# Sheet1.net
KiCad netlist of a schematic drawn in Altium Designer
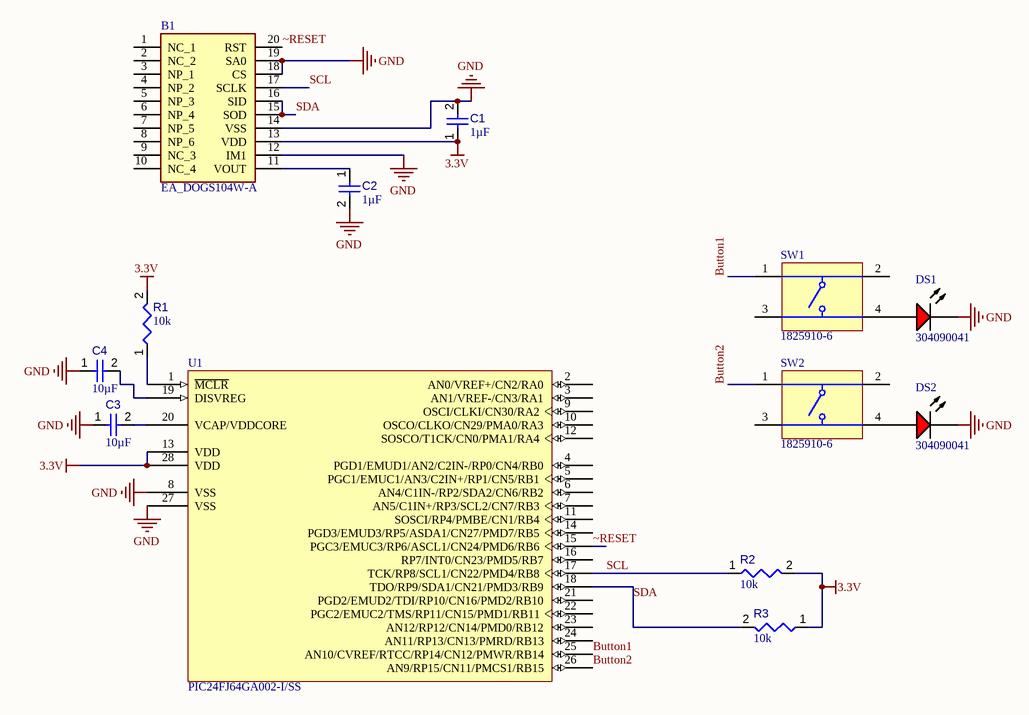
[diagram p0: Sheet1.SchDoc]

(export (version "E")
  (design (tool "Eeschema 10.0.6"))
  (components
    (comp (ref "B1")
      (value "EA_DOGS104W-A")
      (footprint "DIP2540W50P254L3600H260Q20N")
      (description "LED Backlighting LCD MODULE 4X10 WH BKGRND RFLT 2.6mm")
      (fields
        (field (name "MOUSER PART NUMBER") "790-EADOGS104W-A")
        (field (name "MANUFACTURER_PART_NUMBER") "EA DOGS104W-A")
      )
      (libsource (lib "EA_DOGS104W-A") (part "EA_DOGS104W-A"))
    )
    (comp (ref "C1")
      (value "1µF")
      (footprint "CAPC2013X135X45NL10T25")
      (description "Chip Capacitor, 1 uF, +/- 10%, 50 V, 0805 (2012 Metric)")
      (fields (field (name "TOLERANCE") "10%") (field (name "Comment") "Capacitor 1 uF +/- 10% 50 V 0805"))
      (libsource (lib "Egeree Gemta Workspace") (part "CAP-NP-2"))
    )
    (comp (ref "C2")
      (value "1µF")
      (footprint "CAPC2013X135X45NL10T25")
      (description "Chip Capacitor, 1 uF, +/- 10%, 50 V, 0805 (2012 Metric)")
      (fields (field (name "TOLERANCE") "10%") (field (name "Comment") "Capacitor 1 uF +/- 10% 50 V 0805"))
      (libsource (lib "Egeree Gemta Workspace") (part "CAP-NP-2"))
    )
    (comp (ref "C3")
      (value "10µF")
      (footprint "CAPC3216X180X50NL20T25")
      (description "Chip Capacitor, 10 uF, +/- 10%, 16 V, 1206 (3216 Metric)")
      (fields (field (name "TOLERANCE") "10%") (field (name "Comment") "Capacitor 10 uF +/- 10% 16 V 1206"))
      (libsource (lib "Egeree Gemta Workspace") (part "CAP-NP-2"))
    )
    (comp (ref "C4")
      (value "10µF")
      (footprint "CAPC3216X180X50NL20T25")
      (description "Chip Capacitor, 10 uF, +/- 10%, 16 V, 1206 (3216 Metric)")
      (fields (field (name "TOLERANCE") "10%") (field (name "Comment") "Capacitor 10 uF +/- 10% 16 V 1206"))
      (libsource (lib "Egeree Gemta Workspace") (part "CAP-NP-2"))
    )
    (comp (ref "DS1")
      (value "304090041")
      (footprint "LED-2P-2.28-3MM_A")
      (description "Red LED, 80 mW, 30 mA, -25 to 85 degC, 2-Pin THD")
      (fields (field (name "MANUFACTURER") "Shenzhen CGX"))
      (libsource (lib "Egeree Gemta Workspace") (part "LED-RED-AK-2"))
    )
    (comp (ref "DS2")
      (value "304090041")
      (footprint "LED-2P-2.28-3MM_A")
      (description "Red LED, 80 mW, 30 mA, -25 to 85 degC, 2-Pin THD")
      (fields (field (name "MANUFACTURER") "Shenzhen CGX"))
      (libsource (lib "Egeree Gemta Workspace") (part "LED-RED-AK-2"))
    )
    (comp (ref "R1")
      (value "10k")
      (footprint "RESC0402(1005)_L")
      (description "10K 0.063W 1% 0402 (1005 Metric)  SMD")
      (fields (field (name "POWER") "63mW") (field (name "TOLERANCE") "1%"))
      (libsource (lib "Egeree Gemta Workspace") (part "10KR2F"))
    )
    (comp (ref "R2")
      (value "10k")
      (footprint "RESC0402(1005)_L")
      (description "10K 0.063W 1% 0402 (1005 Metric)  SMD")
      (fields (field (name "POWER") "63mW") (field (name "TOLERANCE") "1%"))
      (libsource (lib "Egeree Gemta Workspace") (part "10KR2F"))
    )
    (comp (ref "R3")
      (value "10k")
      (footprint "RESC0402(1005)_L")
      (description "10K 0.063W 1% 0402 (1005 Metric)  SMD")
      (fields (field (name "POWER") "63mW") (field (name "TOLERANCE") "1%"))
      (libsource (lib "Egeree Gemta Workspace") (part "10KR2F"))
    )
    (comp (ref "SW1")
      (value "1825910-6")
      (footprint "TECO-1825910-6_V")
      (description "Tact Switch, SPST-NO, 0.05 A, -35 to 85 degC, 4-Pin THD, RoHS, Bulk")
      (fields (field (name "MANUFACTURER") "TE Connectivity"))
      (libsource (lib "Altium Content Vault") (part "SW-SPST-4_A"))
    )
    (comp (ref "SW2")
      (value "1825910-6")
      (footprint "TECO-1825910-6_V")
      (description "Tact Switch, SPST-NO, 0.05 A, -35 to 85 degC, 4-Pin THD, RoHS, Bulk")
      (fields (field (name "MANUFACTURER") "TE Connectivity"))
      (libsource (lib "Altium Content Vault") (part "SW-SPST-4_A"))
    )
    (comp (ref "U1")
      (value "PIC24FJ64GA002-I/SS")
      (footprint "SSOP-SS28_L")
      (libsource (lib "Altium Content Vault") (part "MC-16B-16GA002-SOIC28"))
    )
  )
  (nets
    (net (code "1") (name "/Button1") (class "Default")
      (node (ref "SW1") (pin "1") (pinfunction "1_1") (pintype "passive"))
      (node (ref "U1") (pin "25") (pinfunction "AN10/CVREF/RTCC/RP14/CN12/PMWR/RB14_25") (pintype "bidirectional"))
    )
    (net (code "2") (name "/Button2") (class "Default")
      (node (ref "SW2") (pin "1") (pinfunction "1_1") (pintype "passive"))
      (node (ref "U1") (pin "26") (pinfunction "AN9/RP15/CN11/PMCS1/RB15_26") (pintype "bidirectional"))
    )
    (net (code "3") (name "/SCL") (class "Default")
      (node (ref "B1") (pin "17") (pinfunction "SCLK_17") (pintype "passive"))
      (node (ref "R2") (pin "1") (pinfunction "1_1") (pintype "passive"))
      (node (ref "U1") (pin "17") (pinfunction "TCK/RP8/SCL1/CN22/PMD4/RB8_17") (pintype "bidirectional"))
    )
    (net (code "4") (name "/SDA") (class "Default")
      (node (ref "B1") (pin "15") (pinfunction "SOD_15") (pintype "passive"))
      (node (ref "B1") (pin "16") (pinfunction "SID_16") (pintype "passive"))
      (node (ref "R3") (pin "2") (pinfunction "2_2") (pintype "passive"))
      (node (ref "U1") (pin "18") (pinfunction "TDO/RP9/SDA1/CN21/PMD3/RB9_18") (pintype "bidirectional"))
    )
    (net (code "5") (name "/~RESET") (class "Default")
      (node (ref "B1") (pin "20") (pinfunction "RST_20") (pintype "passive"))
      (node (ref "U1") (pin "15") (pinfunction "PGC3/EMUC3/RP6/ASCL1/CN24/PMD6/RB6_15") (pintype "bidirectional"))
    )
    (net (code "6") (name "3.3V") (class "Default")
      (node (ref "B1") (pin "13") (pinfunction "VDD_13") (pintype "passive"))
      (node (ref "C1") (pin "1") (pinfunction "1_1") (pintype "passive"))
      (node (ref "R1") (pin "2") (pinfunction "2_2") (pintype "passive"))
      (node (ref "R2") (pin "2") (pinfunction "2_2") (pintype "passive"))
      (node (ref "R3") (pin "1") (pinfunction "1_1") (pintype "passive"))
      (node (ref "U1") (pin "13") (pinfunction "VDD_13") (pintype "power_in"))
      (node (ref "U1") (pin "28") (pinfunction "VDD_28") (pintype "power_in"))
    )
    (net (code "7") (name "GND") (class "Default")
      (node (ref "B1") (pin "12") (pinfunction "IM1_12") (pintype "passive"))
      (node (ref "B1") (pin "14") (pinfunction "VSS_14") (pintype "passive"))
      (node (ref "B1") (pin "18") (pinfunction "CS_18") (pintype "passive"))
      (node (ref "B1") (pin "19") (pinfunction "SA0_19") (pintype "passive"))
      (node (ref "C1") (pin "2") (pinfunction "2_2") (pintype "passive"))
      (node (ref "C2") (pin "2") (pinfunction "2_2") (pintype "passive"))
      (node (ref "C3") (pin "1") (pinfunction "1_1") (pintype "passive"))
      (node (ref "C4") (pin "1") (pinfunction "1_1") (pintype "passive"))
      (node (ref "DS1") (pin "2") (pinfunction "K_2") (pintype "passive"))
      (node (ref "DS2") (pin "2") (pinfunction "K_2") (pintype "passive"))
      (node (ref "U1") (pin "27") (pinfunction "VSS_27") (pintype "power_in"))
      (node (ref "U1") (pin "8") (pinfunction "VSS_8") (pintype "power_in"))
    )
    (net (code "8") (name "Net-(B1-VOUT)") (class "Default")
      (node (ref "B1") (pin "11") (pinfunction "VOUT_11") (pintype "passive"))
      (node (ref "C2") (pin "1") (pinfunction "1_1") (pintype "passive"))
    )
    (net (code "9") (name "Net-(DS1-A)") (class "Default")
      (node (ref "DS1") (pin "1") (pinfunction "A_1") (pintype "passive"))
      (node (ref "SW1") (pin "4") (pinfunction "4_4") (pintype "passive"))
    )
    (net (code "10") (name "Net-(DS2-A)") (class "Default")
      (node (ref "DS2") (pin "1") (pinfunction "A_1") (pintype "passive"))
      (node (ref "SW2") (pin "4") (pinfunction "4_4") (pintype "passive"))
    )
    (net (code "11") (name "Net-(U1-DISVREG)") (class "Default")
      (node (ref "C4") (pin "2") (pinfunction "2_2") (pintype "passive"))
      (node (ref "U1") (pin "19") (pinfunction "DISVREG_19") (pintype "input"))
    )
    (net (code "12") (name "Net-(U1-VCAP{slash}VDDCORE)") (class "Default")
      (node (ref "C3") (pin "2") (pinfunction "2_2") (pintype "passive"))
      (node (ref "U1") (pin "20") (pinfunction "VCAP/VDDCORE_20") (pintype "power_in"))
    )
    (net (code "13") (name "Net-(U1-~{MCLR})") (class "Default")
      (node (ref "R1") (pin "1") (pinfunction "1_1") (pintype "passive"))
      (node (ref "U1") (pin "1") (pinfunction "~{MCLR}_1") (pintype "input"))
    )
    (net (code "14") (name "unconnected-(B1-NC_1-Pad1)") (class "Default")
      (node (ref "B1") (pin "1") (pinfunction "NC_1_1") (pintype "passive"))
    )
    (net (code "15") (name "unconnected-(B1-NC_2-Pad2)") (class "Default")
      (node (ref "B1") (pin "2") (pinfunction "NC_2_2") (pintype "passive"))
    )
    (net (code "16") (name "unconnected-(B1-NC_3-Pad9)") (class "Default")
      (node (ref "B1") (pin "9") (pinfunction "NC_3_9") (pintype "passive"))
    )
    (net (code "17") (name "unconnected-(B1-NC_4-Pad10)") (class "Default")
      (node (ref "B1") (pin "10") (pinfunction "NC_4_10") (pintype "passive"))
    )
    (net (code "18") (name "unconnected-(B1-NP_1-Pad3)") (class "Default")
      (node (ref "B1") (pin "3") (pinfunction "NP_1_3") (pintype "passive"))
    )
    (net (code "19") (name "unconnected-(B1-NP_2-Pad4)") (class "Default")
      (node (ref "B1") (pin "4") (pinfunction "NP_2_4") (pintype "passive"))
    )
    (net (code "20") (name "unconnected-(B1-NP_3-Pad5)") (class "Default")
      (node (ref "B1") (pin "5") (pinfunction "NP_3_5") (pintype "passive"))
    )
    (net (code "21") (name "unconnected-(B1-NP_4-Pad6)") (class "Default")
      (node (ref "B1") (pin "6") (pinfunction "NP_4_6") (pintype "passive"))
    )
    (net (code "22") (name "unconnected-(B1-NP_5-Pad7)") (class "Default")
      (node (ref "B1") (pin "7") (pinfunction "NP_5_7") (pintype "passive"))
    )
    (net (code "23") (name "unconnected-(B1-NP_6-Pad8)") (class "Default")
      (node (ref "B1") (pin "8") (pinfunction "NP_6_8") (pintype "passive"))
    )
    (net (code "24") (name "unconnected-(SW1-Pad2)") (class "Default")
      (node (ref "SW1") (pin "2") (pinfunction "2_2") (pintype "passive"))
    )
    (net (code "25") (name "unconnected-(SW1-Pad3)") (class "Default")
      (node (ref "SW1") (pin "3") (pinfunction "3_3") (pintype "passive"))
    )
    (net (code "26") (name "unconnected-(SW2-Pad2)") (class "Default")
      (node (ref "SW2") (pin "2") (pinfunction "2_2") (pintype "passive"))
    )
    (net (code "27") (name "unconnected-(SW2-Pad3)") (class "Default")
      (node (ref "SW2") (pin "3") (pinfunction "3_3") (pintype "passive"))
    )
    (net (code "28") (name "unconnected-(U1-AN0{slash}VREF+{slash}CN2{slash}RA0-Pad2)") (class "Default")
      (node (ref "U1") (pin "2") (pinfunction "AN0/VREF+/CN2/RA0_2") (pintype "bidirectional"))
    )
    (net (code "29") (name "unconnected-(U1-AN1{slash}VREF-{slash}CN3{slash}RA1-Pad3)") (class "Default")
      (node (ref "U1") (pin "3") (pinfunction "AN1/VREF-/CN3/RA1_3") (pintype "bidirectional"))
    )
    (net (code "30") (name "unconnected-(U1-AN4{slash}C1IN-{slash}RP2{slash}SDA2{slash}CN6{slash}RB2-Pad6)") (class "Default")
      (node (ref "U1") (pin "6") (pinfunction "AN4/C1IN-/RP2/SDA2/CN6/RB2_6") (pintype "bidirectional"))
    )
    (net (code "31") (name "unconnected-(U1-AN5{slash}C1IN+{slash}RP3{slash}SCL2{slash}CN7{slash}RB3-Pad7)") (class "Default")
      (node (ref "U1") (pin "7") (pinfunction "AN5/C1IN+/RP3/SCL2/CN7/RB3_7") (pintype "bidirectional"))
    )
    (net (code "32") (name "unconnected-(U1-AN11{slash}RP13{slash}CN13{slash}PMRD{slash}RB13-Pad24)") (class "Default")
      (node (ref "U1") (pin "24") (pinfunction "AN11/RP13/CN13/PMRD/RB13_24") (pintype "bidirectional"))
    )
    (net (code "33") (name "unconnected-(U1-AN12{slash}RP12{slash}CN14{slash}PMD0{slash}RB12-Pad23)") (class "Default")
      (node (ref "U1") (pin "23") (pinfunction "AN12/RP12/CN14/PMD0/RB12_23") (pintype "bidirectional"))
    )
    (net (code "34") (name "unconnected-(U1-OSCI{slash}CLKI{slash}CN30{slash}RA2-Pad9)") (class "Default")
      (node (ref "U1") (pin "9") (pinfunction "OSCI/CLKI/CN30/RA2_9") (pintype "bidirectional"))
    )
    (net (code "35") (name "unconnected-(U1-OSCO{slash}CLKO{slash}CN29{slash}PMA0{slash}RA3-Pad10)") (class "Default")
      (node (ref "U1") (pin "10") (pinfunction "OSCO/CLKO/CN29/PMA0/RA3_10") (pintype "bidirectional"))
    )
    (net (code "36") (name "unconnected-(U1-PGC1{slash}EMUC1{slash}AN3{slash}C2IN+{slash}RP1{slash}CN5{slash}RB1-Pad5)") (class "Default")
      (node (ref "U1") (pin "5") (pinfunction "PGC1/EMUC1/AN3/C2IN+/RP1/CN5/RB1_5") (pintype "bidirectional"))
    )
    (net (code "37") (name "unconnected-(U1-PGC2{slash}EMUC2{slash}TMS{slash}RP11{slash}CN15{slash}PMD1{slash}RB11-Pad22)") (class "Default")
      (node (ref "U1") (pin "22") (pinfunction "PGC2/EMUC2/TMS/RP11/CN15/PMD1/RB11_22") (pintype "bidirectional"))
    )
    (net (code "38") (name "unconnected-(U1-PGD1{slash}EMUD1{slash}AN2{slash}C2IN-{slash}RP0{slash}CN4{slash}RB0-Pad4)") (class "Default")
      (node (ref "U1") (pin "4") (pinfunction "PGD1/EMUD1/AN2/C2IN-/RP0/CN4/RB0_4") (pintype "bidirectional"))
    )
    (net (code "39") (name "unconnected-(U1-PGD2{slash}EMUD2{slash}TDI{slash}RP10{slash}CN16{slash}PMD2{slash}RB10-Pad21)") (class "Default")
      (node (ref "U1") (pin "21") (pinfunction "PGD2/EMUD2/TDI/RP10/CN16/PMD2/RB10_21") (pintype "bidirectional"))
    )
    (net (code "40") (name "unconnected-(U1-PGD3{slash}EMUD3{slash}RP5{slash}ASDA1{slash}CN27{slash}PMD7{slash}RB5-Pad14)") (class "Default")
      (node (ref "U1") (pin "14") (pinfunction "PGD3/EMUD3/RP5/ASDA1/CN27/PMD7/RB5_14") (pintype "bidirectional"))
    )
    (net (code "41") (name "unconnected-(U1-RP7{slash}INT0{slash}CN23{slash}PMD5{slash}RB7-Pad16)") (class "Default")
      (node (ref "U1") (pin "16") (pinfunction "RP7/INT0/CN23/PMD5/RB7_16") (pintype "bidirectional"))
    )
    (net (code "42") (name "unconnected-(U1-SOSCI{slash}RP4{slash}PMBE{slash}CN1{slash}RB4-Pad11)") (class "Default")
      (node (ref "U1") (pin "11") (pinfunction "SOSCI/RP4/PMBE/CN1/RB4_11") (pintype "bidirectional"))
    )
    (net (code "43") (name "unconnected-(U1-SOSCO{slash}T1CK{slash}CN0{slash}PMA1{slash}RA4-Pad12)") (class "Default")
      (node (ref "U1") (pin "12") (pinfunction "SOSCO/T1CK/CN0/PMA1/RA4_12") (pintype "bidirectional"))
    )
  )
)
